# LEDs_FMU_REV_2A.net
KiCad netlist of a schematic drawn in Altium Designer
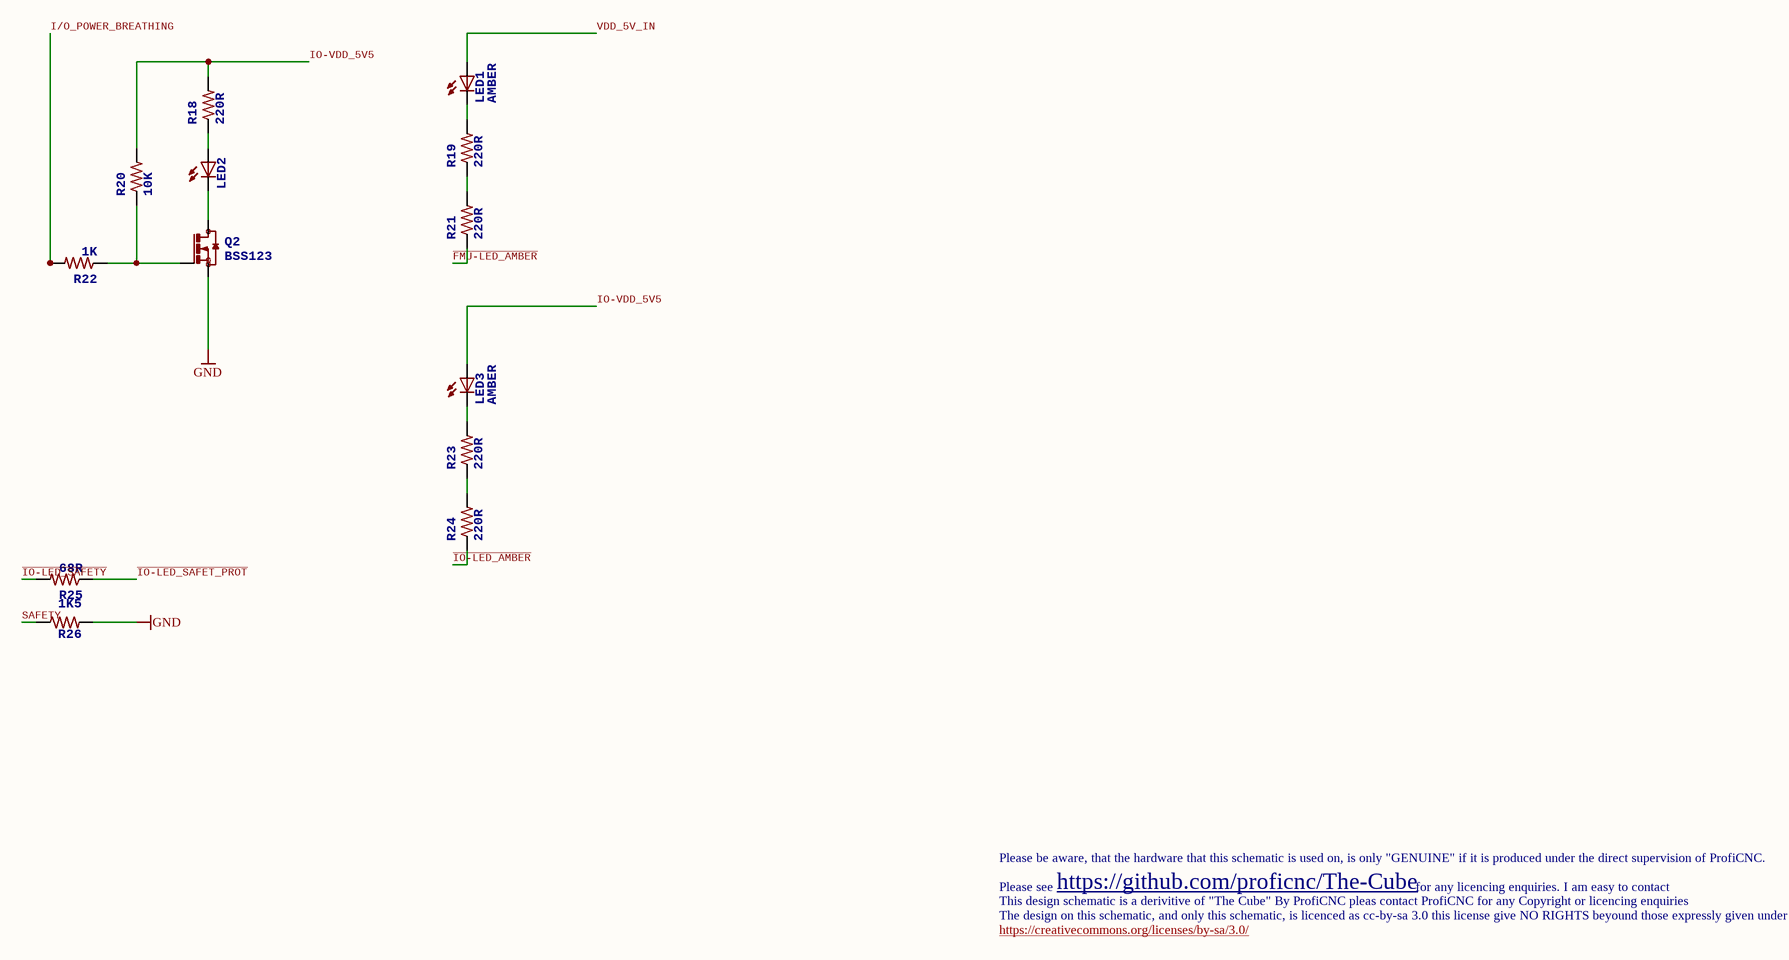
[diagram p0: LEDs_FMU_REV_2A.SchDoc]

(export (version "E")
  (design (tool "Eeschema 10.0.6"))
  (components
    (comp (ref "LED1")
      (value "AMBER")
      (footprint "0603-LED")
      (description "LED 1.6X0.8 DOME ORN CLEAR SMD")
      (libsource (lib "pixhawk2") (part "LED0603"))
    )
    (comp (ref "LED2")
      (value "LED0603_Green")
      (footprint "0603-LED-Blue")
      (description "LED GREEN ROUND CLEAR SMD")
      (libsource (lib "pixhawk2") (part "LED0603_Blue"))
    )
    (comp (ref "LED3")
      (value "AMBER")
      (footprint "0603-LED")
      (description "LED 1.6X0.8 DOME ORN CLEAR SMD")
      (libsource (lib "pixhawk2") (part "LED0603"))
    )
    (comp (ref "Q2")
      (value "BSS123")
      (footprint "SOT23")
      (description "MOSFET N-CH 100V 170MA SOT23-3")
      (libsource (lib "transistor-small-signal") (part "BSS123"))
    )
    (comp (ref "R18")
      (value "220R")
      (footprint "0402-RES")
      (description "RES 220 OHM 1/16W 1% 0402 SMD")
      (libsource (lib "pixhawk2") (part "RESISTOR0402-RES"))
    )
    (comp (ref "R19")
      (value "220R")
      (footprint "0402-RES")
      (description "RES 220 OHM 1/16W 1% 0402 SMD")
      (libsource (lib "pixhawk2") (part "RESISTOR0402-RES"))
    )
    (comp (ref "R20")
      (value "10K")
      (footprint "0402-RES")
      (description "RES 10K OHM 1/16W 1% 0402 SMD")
      (libsource (lib "pixhawk2") (part "RESISTOR0402-RES"))
    )
    (comp (ref "R21")
      (value "220R")
      (footprint "0402-RES")
      (description "RES 220 OHM 1/16W 1% 0402 SMD")
      (libsource (lib "pixhawk2") (part "RESISTOR0402-RES"))
    )
    (comp (ref "R22")
      (value "1K")
      (footprint "0402-RES")
      (description "RES 1K OHM 1/16W 1% 0402")
      (libsource (lib "pixhawk2") (part "RESISTOR0402-RES"))
    )
    (comp (ref "R23")
      (value "220R")
      (footprint "0402-RES")
      (description "RES 220 OHM 1/16W 1% 0402 SMD")
      (libsource (lib "pixhawk2") (part "RESISTOR0402-RES"))
    )
    (comp (ref "R24")
      (value "220R")
      (footprint "0402-RES")
      (description "RES 220 OHM 1/16W 1% 0402 SMD")
      (libsource (lib "pixhawk2") (part "RESISTOR0402-RES"))
    )
    (comp (ref "R25")
      (value "68R")
      (footprint "0402-RES")
      (description "Thick Film Resistors - SMD 0402 68ohms 5% Tol")
      (libsource (lib "pixhawk2") (part "RESISTOR0402-RES"))
    )
    (comp (ref "R26")
      (value "1K5")
      (footprint "0402-RES")
      (description "RES 1.5K OHM 1/16W 1% 0402 SMD")
      (libsource (lib "pixhawk2") (part "RESISTOR0402-RES"))
    )
  )
  (nets
    (net (code "1") (name "/IO-VDD_5V5") (class "Default")
      (node (ref "LED3") (pin "A") (pinfunction "A_A") (pintype "passive"))
      (node (ref "R18") (pin "P$2") (pinfunction "2_P$2") (pintype "passive"))
      (node (ref "R20") (pin "P$2") (pinfunction "2_P$2") (pintype "passive"))
    )
    (net (code "2") (name "/I{slash}O_POWER_BREATHING") (class "Default")
      (node (ref "R22") (pin "P$2") (pinfunction "2_P$2") (pintype "passive"))
    )
    (net (code "3") (name "/SAFETY") (class "Default")
      (node (ref "R26") (pin "P$1") (pinfunction "1_P$1") (pintype "passive"))
    )
    (net (code "4") (name "/VDD_5V_IN") (class "Default")
      (node (ref "LED1") (pin "A") (pinfunction "A_A") (pintype "passive"))
    )
    (net (code "5") (name "/~{FMU-LED_AMBER}") (class "Default")
      (node (ref "R21") (pin "P$1") (pinfunction "1_P$1") (pintype "passive"))
    )
    (net (code "6") (name "/~{IO-LED_AMBER}") (class "Default")
      (node (ref "R24") (pin "P$1") (pinfunction "1_P$1") (pintype "passive"))
    )
    (net (code "7") (name "/~{IO-LED_SAFETY}") (class "Default")
      (node (ref "R25") (pin "P$2") (pinfunction "2_P$2") (pintype "passive"))
    )
    (net (code "8") (name "/~{IO-LED_SAFET_PROT}") (class "Default")
      (node (ref "R25") (pin "P$1") (pinfunction "1_P$1") (pintype "passive"))
    )
    (net (code "9") (name "GND") (class "Default")
      (node (ref "Q2") (pin "2") (pinfunction "S_2") (pintype "passive"))
      (node (ref "R26") (pin "P$2") (pinfunction "2_P$2") (pintype "passive"))
    )
    (net (code "10") (name "Net-(Q2-D)") (class "Default")
      (node (ref "LED2") (pin "C") (pinfunction "C_C") (pintype "passive"))
      (node (ref "Q2") (pin "3") (pinfunction "D_3") (pintype "passive"))
    )
    (net (code "11") (name "Net-(Q2-G)") (class "Default")
      (node (ref "Q2") (pin "1") (pinfunction "G_1") (pintype "passive"))
      (node (ref "R20") (pin "P$1") (pinfunction "1_P$1") (pintype "passive"))
      (node (ref "R22") (pin "P$1") (pinfunction "1_P$1") (pintype "passive"))
    )
    (net (code "12") (name "Net-(R18-1)") (class "Default")
      (node (ref "LED2") (pin "A") (pinfunction "A_A") (pintype "passive"))
      (node (ref "R18") (pin "P$1") (pinfunction "1_P$1") (pintype "passive"))
    )
    (net (code "13") (name "Net-(R19-1)") (class "Default")
      (node (ref "R19") (pin "P$1") (pinfunction "1_P$1") (pintype "passive"))
      (node (ref "R21") (pin "P$2") (pinfunction "2_P$2") (pintype "passive"))
    )
    (net (code "14") (name "Net-(R19-2)") (class "Default")
      (node (ref "LED1") (pin "C") (pinfunction "C_C") (pintype "passive"))
      (node (ref "R19") (pin "P$2") (pinfunction "2_P$2") (pintype "passive"))
    )
    (net (code "15") (name "Net-(R23-1)") (class "Default")
      (node (ref "R23") (pin "P$1") (pinfunction "1_P$1") (pintype "passive"))
      (node (ref "R24") (pin "P$2") (pinfunction "2_P$2") (pintype "passive"))
    )
    (net (code "16") (name "Net-(R23-2)") (class "Default")
      (node (ref "LED3") (pin "C") (pinfunction "C_C") (pintype "passive"))
      (node (ref "R23") (pin "P$2") (pinfunction "2_P$2") (pintype "passive"))
    )
  )
)
